# ProtectionLED.net
KiCad netlist of a schematic drawn in Altium Designer
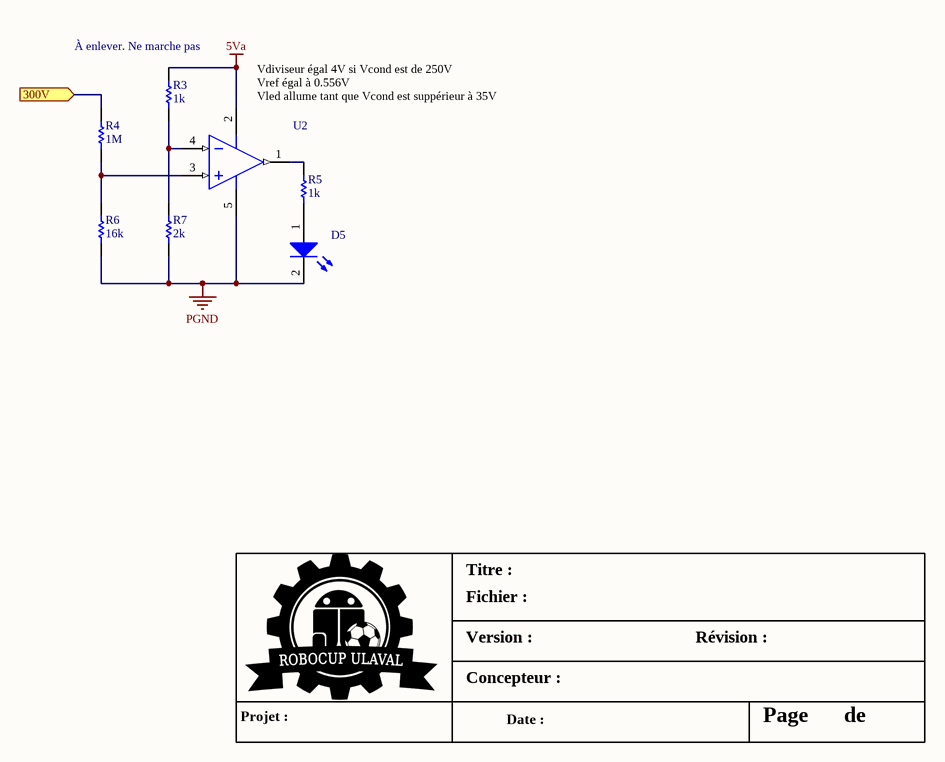
[diagram p0: ProtectionLED.SchDoc]

(export (version "E")
  (design (tool "Eeschema 10.0.6"))
  (components
    (comp (ref "D5")
      (value "APT3216SRCPRV")
      (footprint "1206")
      (description "LED RED CLEAR 1206 SMD")
      (fields (field (name "MANUFACTURER") "Kingbright"))
      (libsource (lib "gamma_gestionkicker") (part "APT3216SRCPRV"))
    )
    (comp (ref "R3")
      (value "RC0603JR-071KL")
      (footprint "0603")
      (description "RES SMD 1K OHM 5% 1/10W 0603")
      (fields
        (field (name "MANUFACTURER") "Yageo")
        (field (name "TOLERANCE") "±5%")
        (field (name "RESISTANCE (OHMS)") "1k")
      )
      (libsource (lib "ResCap") (part "RC0603JR-071KL"))
    )
    (comp (ref "R4")
      (value "RC0603FR-071ML")
      (footprint "0603")
      (description "RES SMD 1M OHM 1% 1/10W 0603")
      (fields
        (field (name "MANUFACTURER") "Yageo")
        (field (name "TOLERANCE") "±1%")
        (field (name "RESISTANCE (OHMS)") "1M")
      )
      (libsource (lib "ResCap") (part "RC0603FR-071ML"))
    )
    (comp (ref "R5")
      (value "RC0603JR-071KL")
      (footprint "0603")
      (description "RES SMD 1K OHM 5% 1/10W 0603")
      (fields
        (field (name "MANUFACTURER") "Yageo")
        (field (name "TOLERANCE") "±5%")
        (field (name "RESISTANCE (OHMS)") "1k")
      )
      (libsource (lib "ResCap") (part "RC0603JR-071KL"))
    )
    (comp (ref "R6")
      (value "ERJ-8GEYJ163V")
      (footprint "1206")
      (description "RES SMD 16K OHM 5% 1/4W 1206")
      (fields
        (field (name "MANUFACTURER") "Panasonic Electronic Components")
        (field (name "TOLERANCE") "±5%")
        (field (name "RESISTANCE (OHMS)") "16k")
      )
      (libsource (lib "ResCap") (part "ERJ-8GEYJ163V"))
    )
    (comp (ref "R7")
      (value "ESR03EZPJ202")
      (footprint "0603")
      (description "RES SMD 2K OHM 5% 1/4W 0603")
      (fields
        (field (name "MANUFACTURER") "Rohm Semiconductor")
        (field (name "TOLERANCE") "±5%")
        (field (name "RESISTANCE (OHMS)") "2k")
      )
      (libsource (lib "ResCap") (part "ESR03EZPJ202"))
    )
    (comp (ref "U2")
      (value "opamp - MCP6L71RT-E/OTCT-ND")
      (footprint "SOT-23-5")
      (description "FET Operational Amplifier")
      (libsource (lib "gamma_gestionkicker") (part "IC OPAMP GP 2MHZ RRO SOT23-5"))
    )
  )
  (nets
    (net (code "1") (name "/300V") (class "Default")
      (node (ref "R4") (pin "2") (pinfunction "2_2") (pintype "passive"))
    )
    (net (code "2") (name "5Va") (class "Default")
      (node (ref "R3") (pin "2") (pinfunction "2_2") (pintype "passive"))
      (node (ref "U2") (pin "2") (pinfunction "V+_2") (pintype "power_in"))
    )
    (net (code "3") (name "Net-(D5-A)") (class "Default")
      (node (ref "D5") (pin "1") (pinfunction "A_1") (pintype "passive"))
      (node (ref "R5") (pin "1") (pinfunction "1_1") (pintype "passive"))
    )
    (net (code "4") (name "Net-(U2-IN+)") (class "Default")
      (node (ref "R4") (pin "1") (pinfunction "1_1") (pintype "passive"))
      (node (ref "R6") (pin "1") (pinfunction "1_1") (pintype "passive"))
      (node (ref "U2") (pin "3") (pinfunction "IN+_3") (pintype "input"))
    )
    (net (code "5") (name "Net-(U2-IN-)") (class "Default")
      (node (ref "R3") (pin "1") (pinfunction "1_1") (pintype "passive"))
      (node (ref "R7") (pin "2") (pinfunction "2_2") (pintype "passive"))
      (node (ref "U2") (pin "4") (pinfunction "IN-_4") (pintype "input"))
    )
    (net (code "6") (name "Net-(U2-OUT)") (class "Default")
      (node (ref "R5") (pin "2") (pinfunction "2_2") (pintype "passive"))
      (node (ref "U2") (pin "1") (pinfunction "OUT_1") (pintype "output"))
    )
    (net (code "7") (name "PGND") (class "Default")
      (node (ref "D5") (pin "2") (pinfunction "K_2") (pintype "passive"))
      (node (ref "R6") (pin "2") (pinfunction "2_2") (pintype "passive"))
      (node (ref "R7") (pin "1") (pinfunction "1_1") (pintype "passive"))
      (node (ref "U2") (pin "5") (pinfunction "V-_5") (pintype "power_in"))
    )
  )
)
